# spi_led.net
KiCad netlist of a schematic drawn in Altium Designer
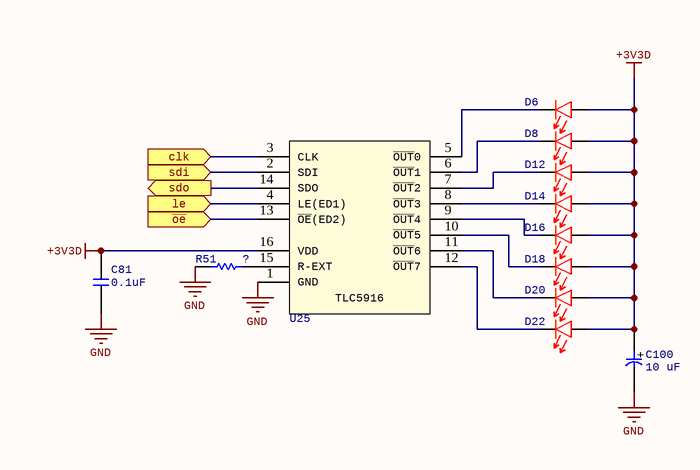
[diagram p0: spi_led.SchDoc]

(export (version "E")
  (design (tool "Eeschema 10.0.6"))
  (components
    (comp (ref "C81")
      (value "0.1uF")
      (footprint "C0603")
      (description "CAP2, CER, 0.1uF, 10%, 25V, 0603")
      (libsource (lib "stdlib") (part "VJ0603Y104KXXAC00"))
    )
    (comp (ref "C100")
      (value "10 uF")
      (footprint "KEMET 1206")
      (description "CAP2, TANT,  10uF, 10%, 10V, 1206")
      (fields
        (field (name "MANUFACTURER") "Kemet")
        (field (name "MANUFACTURER PART NUMBER") "T491A106K010AT")
      )
      (libsource (lib "stdlib") (part "Kemet/T491A106K010AT"))
    )
    (comp (ref "D6")
      (value "Vishay/TLMS1000-GS08")
      (footprint "LED0603")
      (description "LED, 2mA, 0603, Red")
      (libsource (lib "stdlib") (part "Vishay/TLMS1000-GS08"))
    )
    (comp (ref "D8")
      (value "Vishay/TLMS1000-GS08")
      (footprint "LED0603")
      (description "LED, 2mA, 0603, Red")
      (libsource (lib "stdlib") (part "Vishay/TLMS1000-GS08"))
    )
    (comp (ref "D12")
      (value "Vishay/TLMS1000-GS08")
      (footprint "LED0603")
      (description "LED, 2mA, 0603, Red")
      (libsource (lib "stdlib") (part "Vishay/TLMS1000-GS08"))
    )
    (comp (ref "D14")
      (value "Vishay/TLMS1000-GS08")
      (footprint "LED0603")
      (description "LED, 2mA, 0603, Red")
      (libsource (lib "stdlib") (part "Vishay/TLMS1000-GS08"))
    )
    (comp (ref "D16")
      (value "Vishay/TLMS1000-GS08")
      (footprint "LED0603")
      (description "LED, 2mA, 0603, Red")
      (libsource (lib "stdlib") (part "Vishay/TLMS1000-GS08"))
    )
    (comp (ref "D18")
      (value "Vishay/TLMS1000-GS08")
      (footprint "LED0603")
      (description "LED, 2mA, 0603, Red")
      (libsource (lib "stdlib") (part "Vishay/TLMS1000-GS08"))
    )
    (comp (ref "D20")
      (value "Vishay/TLMS1000-GS08")
      (footprint "LED0603")
      (description "LED, 2mA, 0603, Red")
      (libsource (lib "stdlib") (part "Vishay/TLMS1000-GS08"))
    )
    (comp (ref "D22")
      (value "Vishay/TLMS1000-GS08")
      (footprint "LED0603")
      (description "LED, 2mA, 0603, Red")
      (libsource (lib "stdlib") (part "Vishay/TLMS1000-GS08"))
    )
    (comp (ref "R51")
      (value "?")
      (footprint "R0805")
      (description "Placeholder")
      (libsource (lib "stdlib") (part "RES SMD ? OHM 1% 1/10W 0805"))
    )
    (comp (ref "U25")
      (value "TLC5916IPWR")
      (footprint "TSSOP-16")
      (description "LED, Driver, 120mA, 16-TSSOP")
      (fields (field (name "MANUFACTURER") "TEXAS INSTRUMENTS"))
      (libsource (lib "stdlib") (part "TI/TLC5916IPWR TSSOP-16"))
    )
  )
  (nets
    (net (code "1") (name "+3V3D") (class "Default")
      (node (ref "C100") (pin "1") (pinfunction "+_1") (pintype "passive"))
      (node (ref "C81") (pin "2") (pinfunction "2_2") (pintype "passive"))
      (node (ref "D12") (pin "A") (pintype "passive"))
      (node (ref "D14") (pin "A") (pintype "passive"))
      (node (ref "D16") (pin "A") (pintype "passive"))
      (node (ref "D18") (pin "A") (pintype "passive"))
      (node (ref "D20") (pin "A") (pintype "passive"))
      (node (ref "D22") (pin "A") (pintype "passive"))
      (node (ref "D6") (pin "A") (pintype "passive"))
      (node (ref "D8") (pin "A") (pintype "passive"))
      (node (ref "U25") (pin "16") (pinfunction "VDD_16") (pintype "passive"))
    )
    (net (code "2") (name "/clk") (class "Default")
      (node (ref "U25") (pin "3") (pinfunction "CLK_3") (pintype "passive"))
    )
    (net (code "3") (name "/le") (class "Default")
      (node (ref "U25") (pin "4") (pinfunction "LE(ED1)_4") (pintype "passive"))
    )
    (net (code "4") (name "/sdi") (class "Default")
      (node (ref "U25") (pin "2") (pinfunction "SDI_2") (pintype "passive"))
    )
    (net (code "5") (name "/sdo") (class "Default")
      (node (ref "U25") (pin "14") (pinfunction "SDO_14") (pintype "passive"))
    )
    (net (code "6") (name "/~{oe}") (class "Default")
      (node (ref "U25") (pin "13") (pinfunction "~{OE}(ED2)_13") (pintype "passive"))
    )
    (net (code "7") (name "GND") (class "Default")
      (node (ref "C100") (pin "2") (pinfunction "-_2") (pintype "passive"))
      (node (ref "C81") (pin "1") (pinfunction "5_1") (pintype "passive"))
      (node (ref "R51") (pin "1") (pinfunction "1_1") (pintype "passive"))
      (node (ref "U25") (pin "1") (pinfunction "GND_1") (pintype "passive"))
    )
    (net (code "8") (name "Net-(U25-R-EXT)") (class "Default")
      (node (ref "R51") (pin "2") (pinfunction "2_2") (pintype "passive"))
      (node (ref "U25") (pin "15") (pinfunction "R-EXT_15") (pintype "passive"))
    )
    (net (code "9") (name "Net-(U25-~{OUT}0)") (class "Default")
      (node (ref "D6") (pin "C") (pintype "passive"))
      (node (ref "U25") (pin "5") (pinfunction "~{OUT}0_5") (pintype "passive"))
    )
    (net (code "10") (name "Net-(U25-~{OUT}1)") (class "Default")
      (node (ref "D8") (pin "C") (pintype "passive"))
      (node (ref "U25") (pin "6") (pinfunction "~{OUT}1_6") (pintype "passive"))
    )
    (net (code "11") (name "Net-(U25-~{OUT}2)") (class "Default")
      (node (ref "D12") (pin "C") (pintype "passive"))
      (node (ref "U25") (pin "7") (pinfunction "~{OUT}2_7") (pintype "passive"))
    )
    (net (code "12") (name "Net-(U25-~{OUT}3)") (class "Default")
      (node (ref "D14") (pin "C") (pintype "passive"))
      (node (ref "U25") (pin "8") (pinfunction "~{OUT}3_8") (pintype "passive"))
    )
    (net (code "13") (name "Net-(U25-~{OUT}4)") (class "Default")
      (node (ref "D16") (pin "C") (pintype "passive"))
      (node (ref "U25") (pin "9") (pinfunction "~{OUT}4_9") (pintype "passive"))
    )
    (net (code "14") (name "Net-(U25-~{OUT}5)") (class "Default")
      (node (ref "D18") (pin "C") (pintype "passive"))
      (node (ref "U25") (pin "10") (pinfunction "~{OUT}5_10") (pintype "passive"))
    )
    (net (code "15") (name "Net-(U25-~{OUT}6)") (class "Default")
      (node (ref "D20") (pin "C") (pintype "passive"))
      (node (ref "U25") (pin "11") (pinfunction "~{OUT}6_11") (pintype "passive"))
    )
    (net (code "16") (name "Net-(U25-~{OUT}7)") (class "Default")
      (node (ref "D22") (pin "C") (pintype "passive"))
      (node (ref "U25") (pin "12") (pinfunction "~{OUT}7_12") (pintype "passive"))
    )
  )
)
